# Carte_usb_0_8.net
KiCad netlist of a schematic drawn in EAGLE
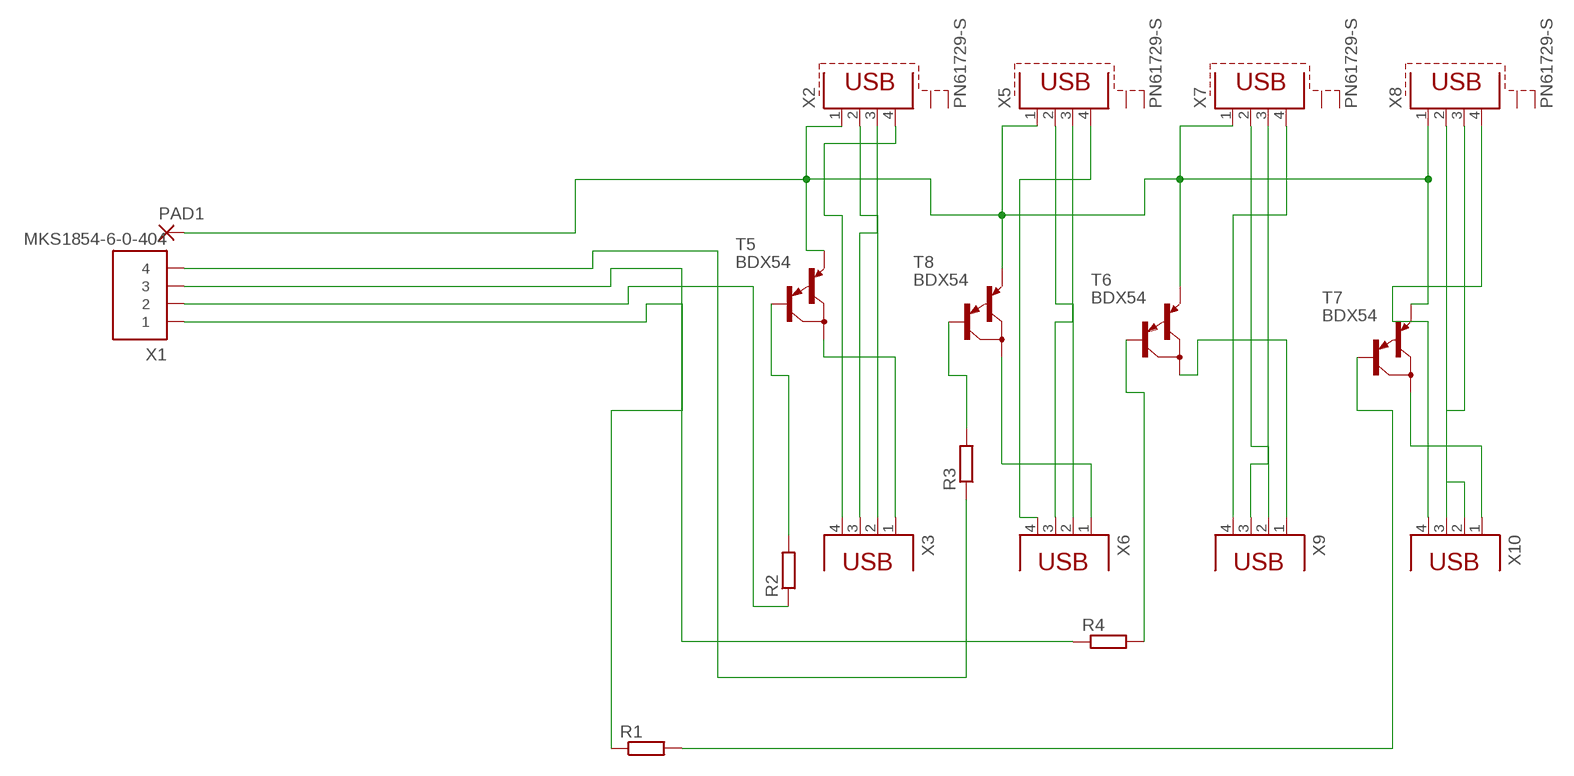
[diagram p0: schematic, sheet 1]

(export (version "E")
  (design (tool "Eeschema 10.0.6"))
  (components
    (comp (ref "PAD1")
      (value "2,54/1,1")
      (footprint "eagle-import:2,54_1,1")
      (libsource (lib "eagle-import") (part "2,54/1,1"))
    )
    (comp (ref "R1")
      (value "R-EU_0207/10")
      (footprint "eagle-import:0207_10")
      (libsource (lib "eagle-import") (part "R-EU_0207/10"))
    )
    (comp (ref "R2")
      (value "R-EU_0207/10")
      (footprint "eagle-import:0207_10")
      (libsource (lib "eagle-import") (part "R-EU_0207/10"))
    )
    (comp (ref "R3")
      (value "R-EU_0207/10")
      (footprint "eagle-import:0207_10")
      (libsource (lib "eagle-import") (part "R-EU_0207/10"))
    )
    (comp (ref "R4")
      (value "R-EU_0207/10")
      (footprint "eagle-import:0207_10")
      (libsource (lib "eagle-import") (part "R-EU_0207/10"))
    )
    (comp (ref "T5")
      (value "BDX54")
      (footprint "eagle-import:TO220")
      (libsource (lib "eagle-import") (part "BDX54"))
    )
    (comp (ref "T6")
      (value "BDX54")
      (footprint "eagle-import:TO220")
      (libsource (lib "eagle-import") (part "BDX54"))
    )
    (comp (ref "T7")
      (value "BDX54")
      (footprint "eagle-import:TO220")
      (libsource (lib "eagle-import") (part "BDX54"))
    )
    (comp (ref "T8")
      (value "BDX54")
      (footprint "eagle-import:TO220")
      (libsource (lib "eagle-import") (part "BDX54"))
    )
    (comp (ref "X1")
      (value "MKS1854-6-0-404")
      (footprint "eagle-import:MKS1854-6-0-404")
      (libsource (lib "eagle-import") (part "MKS1854-6-0-404"))
    )
    (comp (ref "X2")
      (value "PN61729-S")
      (footprint "eagle-import:PN61729-S")
      (libsource (lib "eagle-import") (part "PN61729-S"))
    )
    (comp (ref "X3")
      (value "PN87520")
      (footprint "eagle-import:PN87520")
      (libsource (lib "eagle-import") (part "PN87520"))
    )
    (comp (ref "X5")
      (value "PN61729-S")
      (footprint "eagle-import:PN61729-S")
      (libsource (lib "eagle-import") (part "PN61729-S"))
    )
    (comp (ref "X6")
      (value "PN87520")
      (footprint "eagle-import:PN87520")
      (libsource (lib "eagle-import") (part "PN87520"))
    )
    (comp (ref "X7")
      (value "PN61729-S")
      (footprint "eagle-import:PN61729-S")
      (libsource (lib "eagle-import") (part "PN61729-S"))
    )
    (comp (ref "X8")
      (value "PN61729-S")
      (footprint "eagle-import:PN61729-S")
      (libsource (lib "eagle-import") (part "PN61729-S"))
    )
    (comp (ref "X9")
      (value "PN87520")
      (footprint "eagle-import:PN87520")
      (libsource (lib "eagle-import") (part "PN87520"))
    )
    (comp (ref "X10")
      (value "PN87520")
      (footprint "eagle-import:PN87520")
      (libsource (lib "eagle-import") (part "PN87520"))
    )
  )
  (nets
    (net (code "1") (name "Net-(PAD1-P)") (class "Default")
      (node (ref "PAD1") (pin "1") (pinfunction "P_1") (pintype "passive"))
      (node (ref "T5") (pin "3") (pinfunction "E_3") (pintype "passive"))
      (node (ref "T6") (pin "3") (pinfunction "E_3") (pintype "passive"))
      (node (ref "T7") (pin "3") (pinfunction "E_3") (pintype "passive"))
      (node (ref "T8") (pin "3") (pinfunction "E_3") (pintype "passive"))
      (node (ref "X2") (pin "1") (pinfunction "1_1") (pintype "passive"))
      (node (ref "X5") (pin "1") (pinfunction "1_1") (pintype "passive"))
      (node (ref "X7") (pin "1") (pinfunction "1_1") (pintype "passive"))
      (node (ref "X8") (pin "1") (pinfunction "1_1") (pintype "passive"))
    )
    (net (code "2") (name "Net-(R1-Pad1)") (class "Default")
      (node (ref "R1") (pin "1") (pinfunction "1_1") (pintype "passive"))
      (node (ref "X1") (pin "1") (pinfunction "1_1") (pintype "input"))
    )
    (net (code "3") (name "Net-(R2-Pad1)") (class "Default")
      (node (ref "R2") (pin "1") (pinfunction "1_1") (pintype "passive"))
      (node (ref "X1") (pin "2") (pinfunction "2_2") (pintype "input"))
    )
    (net (code "4") (name "Net-(R3-Pad1)") (class "Default")
      (node (ref "R3") (pin "1") (pinfunction "1_1") (pintype "passive"))
      (node (ref "X1") (pin "4") (pinfunction "4_4") (pintype "input"))
    )
    (net (code "5") (name "Net-(R4-Pad1)") (class "Default")
      (node (ref "R4") (pin "1") (pinfunction "1_1") (pintype "passive"))
      (node (ref "X1") (pin "3") (pinfunction "3_3") (pintype "input"))
    )
    (net (code "6") (name "Net-(T5-B)") (class "Default")
      (node (ref "R2") (pin "2") (pinfunction "2_2") (pintype "passive"))
      (node (ref "T5") (pin "1") (pinfunction "B_1") (pintype "passive"))
    )
    (net (code "7") (name "Net-(T5-C)") (class "Default")
      (node (ref "T5") (pin "2") (pinfunction "C_2") (pintype "passive"))
      (node (ref "X3") (pin "1") (pinfunction "1_1") (pintype "passive"))
    )
    (net (code "8") (name "Net-(T6-B)") (class "Default")
      (node (ref "R4") (pin "2") (pinfunction "2_2") (pintype "passive"))
      (node (ref "T6") (pin "1") (pinfunction "B_1") (pintype "passive"))
    )
    (net (code "9") (name "Net-(T6-C)") (class "Default")
      (node (ref "T6") (pin "2") (pinfunction "C_2") (pintype "passive"))
      (node (ref "X9") (pin "1") (pinfunction "1_1") (pintype "passive"))
    )
    (net (code "10") (name "Net-(T7-B)") (class "Default")
      (node (ref "R1") (pin "2") (pinfunction "2_2") (pintype "passive"))
      (node (ref "T7") (pin "1") (pinfunction "B_1") (pintype "passive"))
    )
    (net (code "11") (name "Net-(T7-C)") (class "Default")
      (node (ref "T7") (pin "2") (pinfunction "C_2") (pintype "passive"))
      (node (ref "X10") (pin "1") (pinfunction "1_1") (pintype "passive"))
    )
    (net (code "12") (name "Net-(T8-B)") (class "Default")
      (node (ref "R3") (pin "2") (pinfunction "2_2") (pintype "passive"))
      (node (ref "T8") (pin "1") (pinfunction "B_1") (pintype "passive"))
    )
    (net (code "13") (name "Net-(T8-C)") (class "Default")
      (node (ref "T8") (pin "2") (pinfunction "C_2") (pintype "passive"))
      (node (ref "X6") (pin "1") (pinfunction "1_1") (pintype "passive"))
    )
    (net (code "14") (name "Net-(X2-Pad2)") (class "Default")
      (node (ref "X2") (pin "2") (pinfunction "2_2") (pintype "passive"))
      (node (ref "X3") (pin "2") (pinfunction "2_2") (pintype "passive"))
    )
    (net (code "15") (name "Net-(X2-Pad3)") (class "Default")
      (node (ref "X2") (pin "3") (pinfunction "3_3") (pintype "passive"))
      (node (ref "X3") (pin "3") (pinfunction "3_3") (pintype "passive"))
    )
    (net (code "16") (name "Net-(X2-Pad4)") (class "Default")
      (node (ref "X2") (pin "4") (pinfunction "4_4") (pintype "passive"))
      (node (ref "X3") (pin "4") (pinfunction "4_4") (pintype "passive"))
    )
    (net (code "17") (name "Net-(X5-Pad2)") (class "Default")
      (node (ref "X5") (pin "2") (pinfunction "2_2") (pintype "passive"))
      (node (ref "X6") (pin "2") (pinfunction "2_2") (pintype "passive"))
    )
    (net (code "18") (name "Net-(X5-Pad3)") (class "Default")
      (node (ref "X5") (pin "3") (pinfunction "3_3") (pintype "passive"))
      (node (ref "X6") (pin "3") (pinfunction "3_3") (pintype "passive"))
    )
    (net (code "19") (name "Net-(X5-Pad4)") (class "Default")
      (node (ref "X5") (pin "4") (pinfunction "4_4") (pintype "passive"))
      (node (ref "X6") (pin "4") (pinfunction "4_4") (pintype "passive"))
    )
    (net (code "20") (name "Net-(X7-Pad2)") (class "Default")
      (node (ref "X7") (pin "2") (pinfunction "2_2") (pintype "passive"))
      (node (ref "X9") (pin "2") (pinfunction "2_2") (pintype "passive"))
    )
    (net (code "21") (name "Net-(X7-Pad3)") (class "Default")
      (node (ref "X7") (pin "3") (pinfunction "3_3") (pintype "passive"))
      (node (ref "X9") (pin "3") (pinfunction "3_3") (pintype "passive"))
    )
    (net (code "22") (name "Net-(X7-Pad4)") (class "Default")
      (node (ref "X7") (pin "4") (pinfunction "4_4") (pintype "passive"))
      (node (ref "X9") (pin "4") (pinfunction "4_4") (pintype "passive"))
    )
    (net (code "23") (name "Net-(X10-Pad2)") (class "Default")
      (node (ref "X10") (pin "2") (pinfunction "2_2") (pintype "passive"))
      (node (ref "X8") (pin "2") (pinfunction "2_2") (pintype "passive"))
    )
    (net (code "24") (name "Net-(X10-Pad3)") (class "Default")
      (node (ref "X10") (pin "3") (pinfunction "3_3") (pintype "passive"))
      (node (ref "X8") (pin "3") (pinfunction "3_3") (pintype "passive"))
    )
    (net (code "25") (name "Net-(X10-Pad4)") (class "Default")
      (node (ref "X10") (pin "4") (pinfunction "4_4") (pintype "passive"))
      (node (ref "X8") (pin "4") (pinfunction "4_4") (pintype "passive"))
    )
    (net (code "26") (name "unconnected-(X2-PadS1)") (class "Default")
      (node (ref "X2") (pin "S1") (pinfunction "S1_S1") (pintype "passive"))
    )
    (net (code "27") (name "unconnected-(X2-PadS2)") (class "Default")
      (node (ref "X2") (pin "S2") (pinfunction "S2_S2") (pintype "passive"))
    )
    (net (code "28") (name "unconnected-(X5-PadS1)") (class "Default")
      (node (ref "X5") (pin "S1") (pinfunction "S1_S1") (pintype "passive"))
    )
    (net (code "29") (name "unconnected-(X5-PadS2)") (class "Default")
      (node (ref "X5") (pin "S2") (pinfunction "S2_S2") (pintype "passive"))
    )
    (net (code "30") (name "unconnected-(X7-PadS1)") (class "Default")
      (node (ref "X7") (pin "S1") (pinfunction "S1_S1") (pintype "passive"))
    )
    (net (code "31") (name "unconnected-(X7-PadS2)") (class "Default")
      (node (ref "X7") (pin "S2") (pinfunction "S2_S2") (pintype "passive"))
    )
    (net (code "32") (name "unconnected-(X8-PadS1)") (class "Default")
      (node (ref "X8") (pin "S1") (pinfunction "S1_S1") (pintype "passive"))
    )
    (net (code "33") (name "unconnected-(X8-PadS2)") (class "Default")
      (node (ref "X8") (pin "S2") (pinfunction "S2_S2") (pintype "passive"))
    )
  )
)
